# ESC.net
KiCad netlist of a schematic drawn in Altium Designer
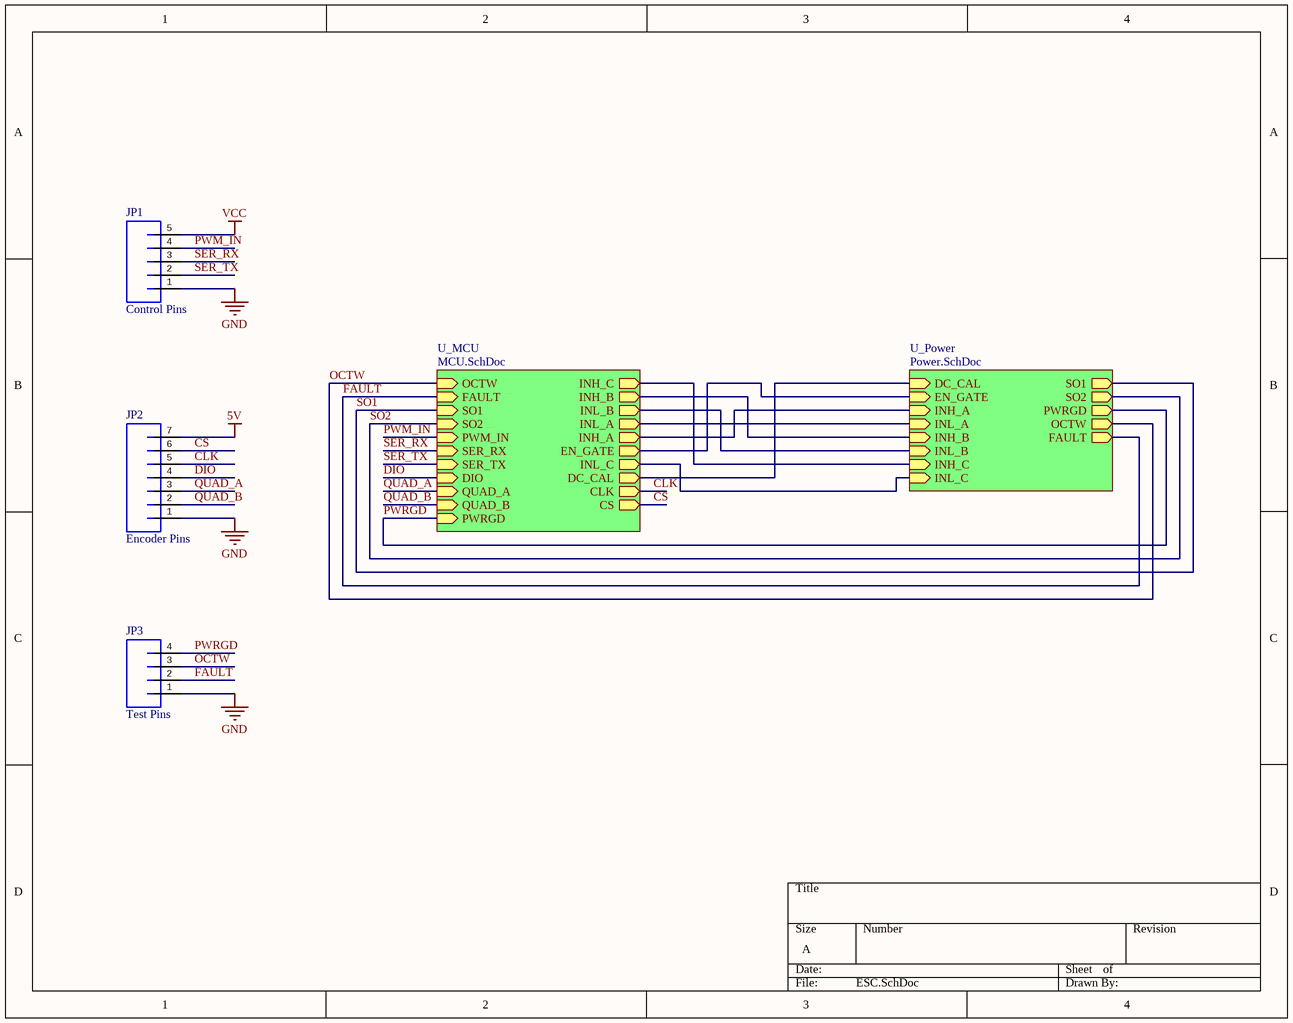
[diagram p0: ESC.SchDoc]

(export (version "E")
  (design (tool "Eeschema 10.0.6"))
  (components
    (comp (ref "JP1")
      (value "Control Pins")
      (footprint "JST-5-PTH-VERT")
      (libsource (lib "Components") (part "JST_5_VERT"))
    )
    (comp (ref "JP2")
      (value "Encoder Pins")
      (footprint "JST-7-PTH-VERT")
      (libsource (lib "Components") (part "JST_7_VERT"))
    )
    (comp (ref "JP3")
      (value "Test Pins")
      (footprint "JST-4-PTH-VERT")
      (libsource (lib "Components") (part "JST_4_VERT"))
    )
  )
  (nets
    (net (code "1") (name "/CLK") (class "Default")
      (node (ref "JP2") (pin "5") (pinfunction "5_5") (pintype "passive"))
    )
    (net (code "2") (name "/CS") (class "Default")
      (node (ref "JP2") (pin "6") (pinfunction "6_6") (pintype "passive"))
    )
    (net (code "4") (name "/DIO") (class "Default")
      (node (ref "JP2") (pin "4") (pinfunction "4_4") (pintype "passive"))
    )
    (net (code "6") (name "/FAULT") (class "Default")
      (node (ref "JP3") (pin "2") (pinfunction "2_2") (pintype "passive"))
    )
    (net (code "13") (name "/OCTW") (class "Default")
      (node (ref "JP3") (pin "3") (pinfunction "3_3") (pintype "passive"))
    )
    (net (code "14") (name "/PWM_IN") (class "Default")
      (node (ref "JP1") (pin "4") (pinfunction "4_4") (pintype "passive"))
    )
    (net (code "15") (name "/PWRGD") (class "Default")
      (node (ref "JP3") (pin "4") (pinfunction "4_4") (pintype "passive"))
    )
    (net (code "16") (name "/QUAD_A") (class "Default")
      (node (ref "JP2") (pin "3") (pinfunction "3_3") (pintype "passive"))
    )
    (net (code "17") (name "/QUAD_B") (class "Default")
      (node (ref "JP2") (pin "2") (pinfunction "2_2") (pintype "passive"))
    )
    (net (code "18") (name "/SER_RX") (class "Default")
      (node (ref "JP1") (pin "3") (pinfunction "3_3") (pintype "passive"))
    )
    (net (code "19") (name "/SER_TX") (class "Default")
      (node (ref "JP1") (pin "2") (pinfunction "2_2") (pintype "passive"))
    )
    (net (code "22") (name "5V") (class "Default")
      (node (ref "JP2") (pin "7") (pinfunction "7_7") (pintype "passive"))
    )
    (net (code "23") (name "GND") (class "Default")
      (node (ref "JP1") (pin "1") (pinfunction "1_1") (pintype "passive"))
      (node (ref "JP2") (pin "1") (pinfunction "1_1") (pintype "passive"))
      (node (ref "JP3") (pin "1") (pinfunction "1_1") (pintype "passive"))
    )
    (net (code "24") (name "VCC") (class "Default")
      (node (ref "JP1") (pin "5") (pinfunction "5_5") (pintype "passive"))
    )
  )
)
